# voltage_control.net
KiCad netlist of a schematic drawn in EAGLE
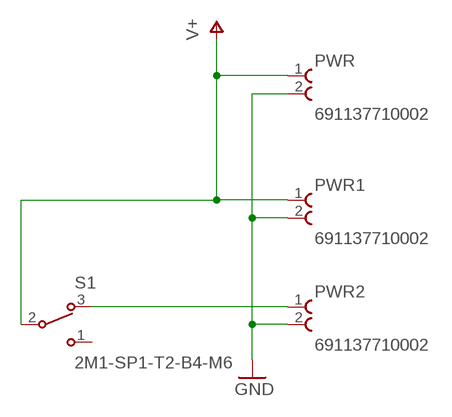
[diagram p0: schematic, sheet 1]

(export (version "E")
  (design (tool "Eeschema 10.0.6"))
  (components
    (comp (ref "PWR")
      (value "691137710002")
      (footprint "eagle-import:691137710002")
      (fields (field (name "MF") "Wurth Electronics"))
      (libsource (lib "eagle-import") (part "691137710002"))
    )
    (comp (ref "PWR1")
      (value "691137710002")
      (footprint "eagle-import:691137710002")
      (fields (field (name "MF") "Wurth Electronics"))
      (libsource (lib "eagle-import") (part "691137710002"))
    )
    (comp (ref "PWR2")
      (value "691137710002")
      (footprint "eagle-import:691137710002")
      (fields (field (name "MF") "Wurth Electronics"))
      (libsource (lib "eagle-import") (part "691137710002"))
    )
    (comp (ref "S1")
      (value "2M1-SP1-T2-B4-M6")
      (footprint "eagle-import:2M1-SP1-T2-B4-M6")
      (libsource (lib "eagle-import") (part "2M1-SP1-T2-B4-M6"))
    )
  )
  (nets
    (net (code "1") (name "GND") (class "Default")
      (node (ref "PWR") (pin "2") (pinfunction "2_2") (pintype "passive"))
      (node (ref "PWR1") (pin "2") (pinfunction "2_2") (pintype "passive"))
      (node (ref "PWR2") (pin "2") (pinfunction "2_2") (pintype "passive"))
    )
    (net (code "2") (name "Net-(S1-O)") (class "Default")
      (node (ref "PWR2") (pin "1") (pinfunction "1_1") (pintype "passive"))
      (node (ref "S1") (pin "3") (pinfunction "O_3") (pintype "passive"))
    )
    (net (code "3") (name "V+") (class "Default")
      (node (ref "PWR") (pin "1") (pinfunction "1_1") (pintype "passive"))
      (node (ref "PWR1") (pin "1") (pinfunction "1_1") (pintype "passive"))
      (node (ref "S1") (pin "2") (pinfunction "P_2") (pintype "passive"))
    )
    (net (code "4") (name "unconnected-(S1-S-Pad1)") (class "Default")
      (node (ref "S1") (pin "1") (pinfunction "S_1") (pintype "passive"))
    )
  )
)
